# magnetorquer_board_CURRENT.net
KiCad netlist of a schematic drawn in EAGLE
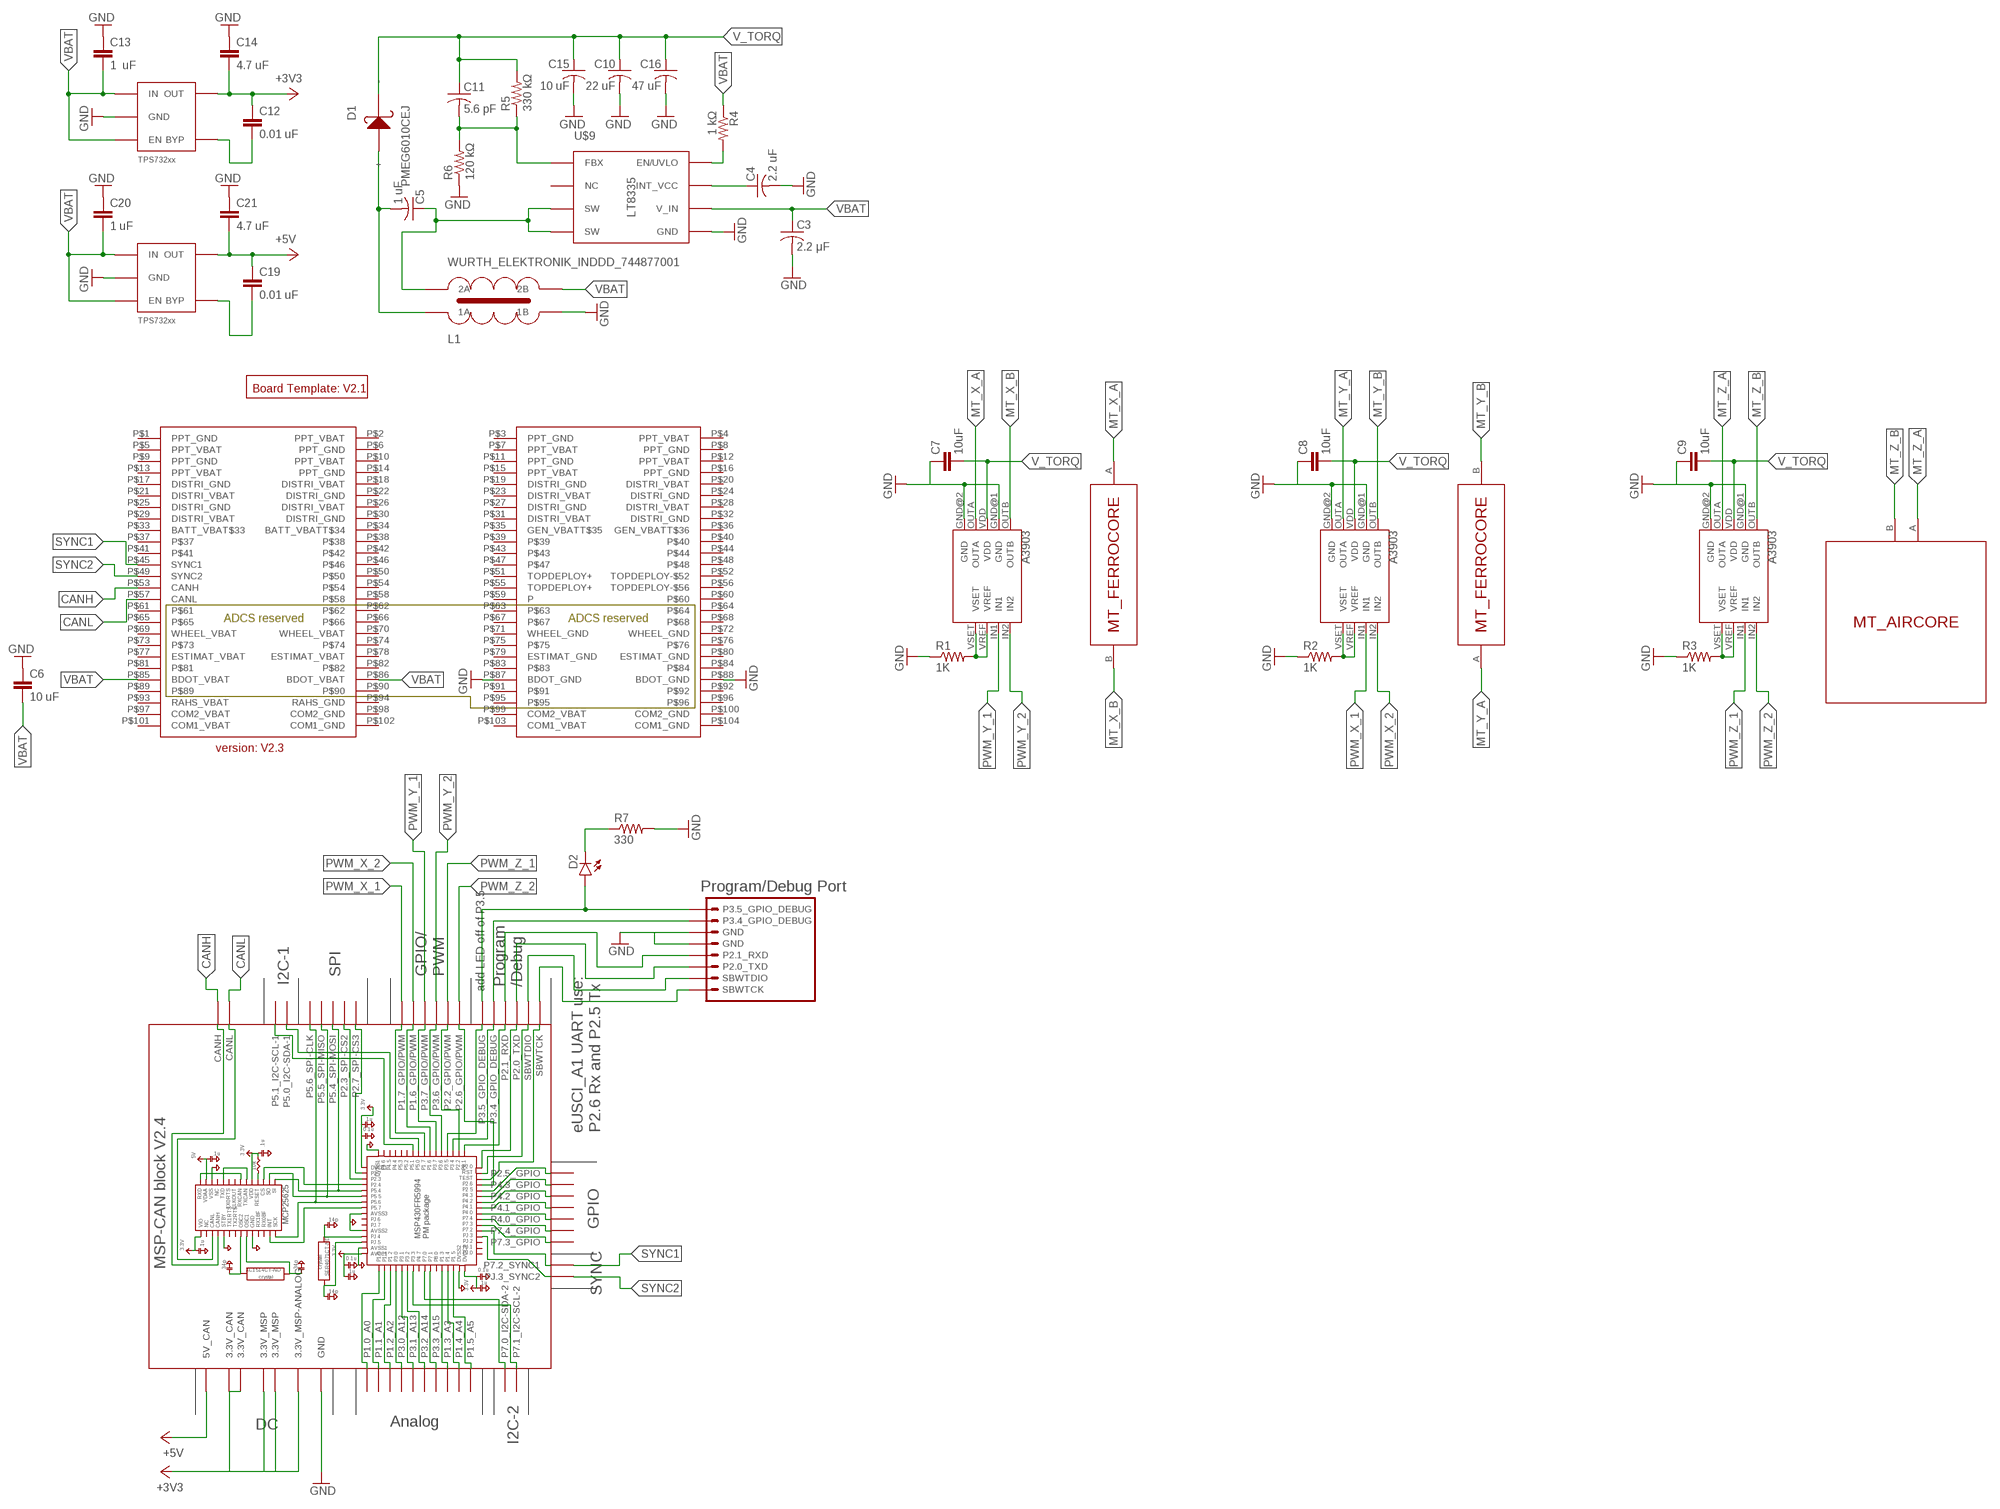
[diagram p0: schematic, sheet 1]

(export (version "E")
  (design (tool "Eeschema 10.0.6"))
  (components
    (comp (ref "C3")
      (value "2.2 μF")
      (footprint "eagle-import:C0805")
      (libsource (lib "eagle-import") (part "C-USC0805"))
    )
    (comp (ref "C4")
      (value "2.2 uF")
      (footprint "eagle-import:C0805")
      (libsource (lib "eagle-import") (part "C-USC0805"))
    )
    (comp (ref "C5")
      (value "1 uF")
      (footprint "eagle-import:C0805")
      (libsource (lib "eagle-import") (part "C-USC0805"))
    )
    (comp (ref "C6")
      (value "10 uF")
      (footprint "eagle-import:0805")
      (libsource (lib "eagle-import") (part "CAPACITOR0805"))
    )
    (comp (ref "C7")
      (value "10uF")
      (footprint "eagle-import:0805")
      (libsource (lib "eagle-import") (part "CAPACITOR0805"))
    )
    (comp (ref "C8")
      (value "10uF")
      (footprint "eagle-import:0805")
      (libsource (lib "eagle-import") (part "CAPACITOR0805"))
    )
    (comp (ref "C9")
      (value "10uF")
      (footprint "eagle-import:0805")
      (libsource (lib "eagle-import") (part "CAPACITOR0805"))
    )
    (comp (ref "C10")
      (value "22 uF")
      (footprint "eagle-import:C1206")
      (libsource (lib "eagle-import") (part "C-USC1206"))
    )
    (comp (ref "C11")
      (value "5.6 pF")
      (footprint "eagle-import:C0805")
      (libsource (lib "eagle-import") (part "C-USC0805"))
    )
    (comp (ref "C12")
      (value "0.01 uF")
      (footprint "eagle-import:0805")
      (libsource (lib "eagle-import") (part "CAPACITOR0805"))
    )
    (comp (ref "C13")
      (value "1 uF")
      (footprint "eagle-import:0805")
      (libsource (lib "eagle-import") (part "CAPACITOR0805"))
    )
    (comp (ref "C14")
      (value "4.7 uF")
      (footprint "eagle-import:0805")
      (libsource (lib "eagle-import") (part "CAPACITOR0805"))
    )
    (comp (ref "C15")
      (value "10 uF")
      (footprint "eagle-import:C0805")
      (libsource (lib "eagle-import") (part "C-USC0805"))
    )
    (comp (ref "C16")
      (value "47 uF")
      (footprint "eagle-import:C1206")
      (libsource (lib "eagle-import") (part "C-USC1206"))
    )
    (comp (ref "C19")
      (value "0.01 uF")
      (footprint "eagle-import:0805")
      (libsource (lib "eagle-import") (part "CAPACITOR0805"))
    )
    (comp (ref "C20")
      (value "1 uF")
      (footprint "eagle-import:0805")
      (libsource (lib "eagle-import") (part "CAPACITOR0805"))
    )
    (comp (ref "C21")
      (value "4.7 uF")
      (footprint "eagle-import:0805")
      (libsource (lib "eagle-import") (part "CAPACITOR0805"))
    )
    (comp (ref "D1")
      (value "PMEG6010CEJ")
      (footprint "eagle-import:SC-90")
      (libsource (lib "eagle-import") (part "PMEG6010CEJ"))
    )
    (comp (ref "D2")
      (value "LED")
      (footprint "eagle-import:LED-1206")
      (libsource (lib "eagle-import") (part "LED"))
    )
    (comp (ref "L1")
      (value "WURTH_ELEKTRONIK_INDDD_744877001")
      (footprint "eagle-import:WURTH_ELEKTRONIK_INDDD_744877001")
      (libsource (lib "eagle-import") (part "WURTH_ELEKTRONIK_INDDD_744877001"))
    )
    (comp (ref "LDO_3V1")
      (value "TPS732XX")
      (footprint "eagle-import:SOT-23-5")
      (libsource (lib "eagle-import") (part "TPS732XX"))
    )
    (comp (ref "LDO_5V1")
      (value "TPS732XX")
      (footprint "eagle-import:SOT-23-5")
      (libsource (lib "eagle-import") (part "TPS732XX"))
    )
    (comp (ref "R1")
      (value "1K")
      (footprint "eagle-import:R0603")
      (libsource (lib "eagle-import") (part "R-US_R0603"))
    )
    (comp (ref "R2")
      (value "1K")
      (footprint "eagle-import:R0603")
      (libsource (lib "eagle-import") (part "R-US_R0603"))
    )
    (comp (ref "R3")
      (value "1K")
      (footprint "eagle-import:R0603")
      (libsource (lib "eagle-import") (part "R-US_R0603"))
    )
    (comp (ref "R4")
      (value "1 kΩ")
      (footprint "eagle-import:0805")
      (libsource (lib "eagle-import") (part "RESISTOR0805"))
    )
    (comp (ref "R5")
      (value "330 kΩ")
      (footprint "eagle-import:0805")
      (libsource (lib "eagle-import") (part "RESISTOR0805"))
    )
    (comp (ref "R6")
      (value "120 kΩ")
      (footprint "eagle-import:0805")
      (libsource (lib "eagle-import") (part "RESISTOR0805"))
    )
    (comp (ref "R7")
      (value "330")
      (footprint "eagle-import:0805")
      (libsource (lib "eagle-import") (part "RESISTOR0805"))
    )
    (comp (ref "U$1")
      (value "PC104_CONNECTOR")
      (footprint "eagle-import:PC104_CONNECTOR")
      (libsource (lib "eagle-import") (part "PC104_CONNECTOR"))
    )
    (comp (ref "U$2")
      (value "BOARD_TEMPLATE1")
      (footprint "eagle-import:BOARD_TEMPLATE")
      (libsource (lib "eagle-import") (part "BOARD_TEMPLATE1"))
    )
    (comp (ref "U$3")
      (value "MT_AIRCORE")
      (footprint "eagle-import:MT_AIRCORE")
      (libsource (lib "eagle-import") (part "MT_AIRCORE"))
    )
    (comp (ref "U$4")
      (value "MT_FERROCORE")
      (footprint "eagle-import:MT_FERROCORE")
      (libsource (lib "eagle-import") (part "MT_FERROCORE"))
    )
    (comp (ref "U$5")
      (value "MT_FERROCORE")
      (footprint "eagle-import:MT_FERROCORE")
      (libsource (lib "eagle-import") (part "MT_FERROCORE"))
    )
    (comp (ref "U$7")
      (value "MSP-CAN_BLOCK")
      (footprint "eagle-import:MSP-CAN_BLOCK")
      (libsource (lib "eagle-import") (part "MSP-CAN_BLOCK"))
    )
    (comp (ref "U$8")
      (value "PROGRAM/DEBUG_PORT")
      (footprint "eagle-import:1X08_CONNECTOR")
      (libsource (lib "eagle-import") (part "PROGRAM/DEBUG_PORT"))
    )
    (comp (ref "U$9")
      (value "LT8335")
      (footprint "eagle-import:DDB")
      (libsource (lib "eagle-import") (part "LT8335"))
    )
    (comp (ref "U1")
      (value "A3903")
      (footprint "eagle-import:DFN-8EE")
      (libsource (lib "eagle-import") (part "A3903"))
    )
    (comp (ref "U2")
      (value "A3903")
      (footprint "eagle-import:DFN-8EE")
      (libsource (lib "eagle-import") (part "A3903"))
    )
    (comp (ref "U3")
      (value "A3903")
      (footprint "eagle-import:DFN-8EE")
      (libsource (lib "eagle-import") (part "A3903"))
    )
  )
  (nets
    (net (code "1") (name "+3V3") (class "Default")
      (node (ref "C12") (pin "1") (pinfunction "1_1") (pintype "passive"))
      (node (ref "C14") (pin "2") (pinfunction "2_2") (pintype "passive"))
      (node (ref "LDO_3V1") (pin "P$5") (pinfunction "OUT_P$5") (pintype "bidirectional"))
      (node (ref "U$7") (pin "3.3V@CAN1") (pinfunction "3.3V_CAN_3.3V@CAN1") (pintype "bidirectional"))
      (node (ref "U$7") (pin "3.3V@CAN2") (pinfunction "3.3V_CAN_3.3V@CAN2") (pintype "bidirectional"))
      (node (ref "U$7") (pin "3.3V@MSP1") (pinfunction "3.3V_MSP_3.3V@MSP1") (pintype "bidirectional"))
      (node (ref "U$7") (pin "3.3V@MSP2") (pinfunction "3.3V_MSP_3.3V@MSP2") (pintype "bidirectional"))
      (node (ref "U$7") (pin "3.3V_ANALOG@MSP2") (pinfunction "3.3V_MSP-ANALOG_3.3V_ANALOG@MSP2") (pintype "bidirectional"))
    )
    (net (code "2") (name "+5V") (class "Default")
      (node (ref "C19") (pin "1") (pinfunction "1_1") (pintype "passive"))
      (node (ref "C21") (pin "2") (pinfunction "2_2") (pintype "passive"))
      (node (ref "LDO_5V1") (pin "P$5") (pinfunction "OUT_P$5") (pintype "bidirectional"))
      (node (ref "U$7") (pin "5V") (pinfunction "5V_CAN_5V") (pintype "bidirectional"))
    )
    (net (code "3") (name "CANH") (class "Default")
      (node (ref "U$1") (pin "P$53") (pinfunction "CANH_P$53") (pintype "bidirectional"))
      (node (ref "U$7") (pin "CANH") (pinfunction "CANH_CANH") (pintype "bidirectional"))
    )
    (net (code "4") (name "CANL") (class "Default")
      (node (ref "U$1") (pin "P$57") (pinfunction "CANL_P$57") (pintype "bidirectional"))
      (node (ref "U$7") (pin "CANL") (pinfunction "CANL_CANL") (pintype "bidirectional"))
    )
    (net (code "5") (name "GND") (class "Default")
      (node (ref "C10") (pin "2") (pinfunction "2_2") (pintype "passive"))
      (node (ref "C13") (pin "1") (pinfunction "1_1") (pintype "passive"))
      (node (ref "C14") (pin "1") (pinfunction "1_1") (pintype "passive"))
      (node (ref "C15") (pin "2") (pinfunction "2_2") (pintype "passive"))
      (node (ref "C16") (pin "2") (pinfunction "2_2") (pintype "passive"))
      (node (ref "C20") (pin "1") (pinfunction "1_1") (pintype "passive"))
      (node (ref "C21") (pin "1") (pinfunction "1_1") (pintype "passive"))
      (node (ref "C3") (pin "2") (pinfunction "2_2") (pintype "passive"))
      (node (ref "C4") (pin "2") (pinfunction "2_2") (pintype "passive"))
      (node (ref "C6") (pin "1") (pinfunction "1_1") (pintype "passive"))
      (node (ref "C7") (pin "1") (pinfunction "1_1") (pintype "passive"))
      (node (ref "C8") (pin "1") (pinfunction "1_1") (pintype "passive"))
      (node (ref "C9") (pin "1") (pinfunction "1_1") (pintype "passive"))
      (node (ref "L1") (pin "P$2") (pinfunction "1B_P$2") (pintype "bidirectional"))
      (node (ref "LDO_3V1") (pin "P$2") (pinfunction "GND_P$2") (pintype "bidirectional"))
      (node (ref "LDO_5V1") (pin "P$2") (pinfunction "GND_P$2") (pintype "bidirectional"))
      (node (ref "R1") (pin "1") (pinfunction "1_1") (pintype "passive"))
      (node (ref "R2") (pin "1") (pinfunction "1_1") (pintype "passive"))
      (node (ref "R3") (pin "1") (pinfunction "1_1") (pintype "passive"))
      (node (ref "R6") (pin "1") (pinfunction "1_1") (pintype "passive"))
      (node (ref "R7") (pin "2") (pinfunction "2_2") (pintype "passive"))
      (node (ref "U$1") (pin "P$87") (pinfunction "BDOT_GND_P$87") (pintype "bidirectional"))
      (node (ref "U$1") (pin "P$88") (pinfunction "BDOT_GND_P$88") (pintype "bidirectional"))
      (node (ref "U$7") (pin "GND@1") (pinfunction "GND_GND@1") (pintype "bidirectional"))
      (node (ref "U$7") (pin "GND@10") (pinfunction "GND_GND@10") (pintype "bidirectional"))
      (node (ref "U$7") (pin "GND@11") (pinfunction "GND_GND@11") (pintype "bidirectional"))
      (node (ref "U$7") (pin "GND@12") (pinfunction "GND_GND@12") (pintype "bidirectional"))
      (node (ref "U$7") (pin "GND@13") (pinfunction "GND_GND@13") (pintype "bidirectional"))
      (node (ref "U$7") (pin "GND@14") (pinfunction "GND_GND@14") (pintype "bidirectional"))
      (node (ref "U$7") (pin "GND@15") (pinfunction "GND_GND@15") (pintype "bidirectional"))
      (node (ref "U$7") (pin "GND@16") (pinfunction "GND_GND@16") (pintype "bidirectional"))
      (node (ref "U$7") (pin "GND@17") (pinfunction "GND_GND@17") (pintype "bidirectional"))
      (node (ref "U$7") (pin "GND@2") (pinfunction "GND_GND@2") (pintype "bidirectional"))
      (node (ref "U$7") (pin "GND@26") (pinfunction "GND_GND@26") (pintype "bidirectional"))
      (node (ref "U$7") (pin "GND@3") (pinfunction "GND_GND@3") (pintype "bidirectional"))
      (node (ref "U$7") (pin "GND@4") (pinfunction "GND_GND@4") (pintype "bidirectional"))
      (node (ref "U$7") (pin "GND@5") (pinfunction "GND_GND@5") (pintype "bidirectional"))
      (node (ref "U$7") (pin "GND@7") (pinfunction "GND_GND@7") (pintype "bidirectional"))
      (node (ref "U$7") (pin "GND@8") (pinfunction "GND_GND@8") (pintype "bidirectional"))
      (node (ref "U$7") (pin "GND@9") (pinfunction "GND_GND@9") (pintype "bidirectional"))
      (node (ref "U$8") (pin "5") (pinfunction "GND_5") (pintype "bidirectional"))
      (node (ref "U$8") (pin "6") (pinfunction "GND_6") (pintype "bidirectional"))
      (node (ref "U$9") (pin "GND") (pinfunction "GND_GND") (pintype "bidirectional"))
      (node (ref "U$9") (pin "P$5") (pinfunction "GND_P$5") (pintype "bidirectional"))
      (node (ref "U1") (pin "GND@1") (pinfunction "GND_GND@1") (pintype "power_in"))
      (node (ref "U1") (pin "GND@2") (pinfunction "GND_GND@2") (pintype "power_in"))
      (node (ref "U2") (pin "GND@1") (pinfunction "GND_GND@1") (pintype "power_in"))
      (node (ref "U2") (pin "GND@2") (pinfunction "GND_GND@2") (pintype "power_in"))
      (node (ref "U3") (pin "GND@1") (pinfunction "GND_GND@1") (pintype "power_in"))
      (node (ref "U3") (pin "GND@2") (pinfunction "GND_GND@2") (pintype "power_in"))
    )
    (net (code "6") (name "MT_X_A") (class "Default")
      (node (ref "U$4") (pin "A") (pinfunction "A_A") (pintype "bidirectional"))
      (node (ref "U1") (pin "OUTA") (pinfunction "OUTA_OUTA") (pintype "output"))
    )
    (net (code "7") (name "MT_X_B") (class "Default")
      (node (ref "U$4") (pin "B") (pinfunction "B_B") (pintype "bidirectional"))
      (node (ref "U1") (pin "OUTB") (pinfunction "OUTB_OUTB") (pintype "output"))
    )
    (net (code "8") (name "MT_Y_A") (class "Default")
      (node (ref "U$5") (pin "A") (pinfunction "A_A") (pintype "bidirectional"))
      (node (ref "U2") (pin "OUTA") (pinfunction "OUTA_OUTA") (pintype "output"))
    )
    (net (code "9") (name "MT_Y_B") (class "Default")
      (node (ref "U$5") (pin "B") (pinfunction "B_B") (pintype "bidirectional"))
      (node (ref "U2") (pin "OUTB") (pinfunction "OUTB_OUTB") (pintype "output"))
    )
    (net (code "10") (name "MT_Z_A") (class "Default")
      (node (ref "U$3") (pin "A") (pinfunction "A_A") (pintype "bidirectional"))
      (node (ref "U3") (pin "OUTA") (pinfunction "OUTA_OUTA") (pintype "output"))
    )
    (net (code "11") (name "MT_Z_B") (class "Default")
      (node (ref "U$3") (pin "B") (pinfunction "B_B") (pintype "bidirectional"))
      (node (ref "U3") (pin "OUTB") (pinfunction "OUTB_OUTB") (pintype "output"))
    )
    (net (code "12") (name "Net-(D1-+)") (class "Default")
      (node (ref "C5") (pin "2") (pinfunction "2_2") (pintype "passive"))
      (node (ref "D1") (pin "P$1") (pinfunction "+_P$1") (pintype "bidirectional"))
      (node (ref "L1") (pin "P$1") (pinfunction "1A_P$1") (pintype "bidirectional"))
    )
    (net (code "13") (name "Net-(D2-PadC)") (class "Default")
      (node (ref "D2") (pin "C") (pinfunction "C_C") (pintype "passive"))
      (node (ref "R7") (pin "1") (pinfunction "1_1") (pintype "passive"))
    )
    (net (code "14") (name "Net-(L1-2A)") (class "Default")
      (node (ref "C5") (pin "1") (pinfunction "1_1") (pintype "passive"))
      (node (ref "L1") (pin "P$3") (pinfunction "2A_P$3") (pintype "bidirectional"))
      (node (ref "U$9") (pin "P$3") (pinfunction "SW_P$3") (pintype "bidirectional"))
      (node (ref "U$9") (pin "P$4") (pinfunction "SW_P$4") (pintype "bidirectional"))
    )
    (net (code "15") (name "Net-(LDO_3V1-BYP)") (class "Default")
      (node (ref "C12") (pin "2") (pinfunction "2_2") (pintype "passive"))
      (node (ref "LDO_3V1") (pin "P$4") (pinfunction "BYP_P$4") (pintype "bidirectional"))
    )
    (net (code "16") (name "Net-(LDO_5V1-BYP)") (class "Default")
      (node (ref "C19") (pin "2") (pinfunction "2_2") (pintype "passive"))
      (node (ref "LDO_5V1") (pin "P$4") (pinfunction "BYP_P$4") (pintype "bidirectional"))
    )
    (net (code "17") (name "Net-(R1-Pad2)") (class "Default")
      (node (ref "R1") (pin "2") (pinfunction "2_2") (pintype "passive"))
      (node (ref "U1") (pin "VREF") (pinfunction "VREF_VREF") (pintype "power_in"))
      (node (ref "U1") (pin "VSET") (pinfunction "VSET_VSET") (pintype "bidirectional"))
    )
    (net (code "18") (name "Net-(R2-Pad2)") (class "Default")
      (node (ref "R2") (pin "2") (pinfunction "2_2") (pintype "passive"))
      (node (ref "U2") (pin "VREF") (pinfunction "VREF_VREF") (pintype "power_in"))
      (node (ref "U2") (pin "VSET") (pinfunction "VSET_VSET") (pintype "bidirectional"))
    )
    (net (code "19") (name "Net-(R3-Pad2)") (class "Default")
      (node (ref "R3") (pin "2") (pinfunction "2_2") (pintype "passive"))
      (node (ref "U3") (pin "VREF") (pinfunction "VREF_VREF") (pintype "power_in"))
      (node (ref "U3") (pin "VSET") (pinfunction "VSET_VSET") (pintype "bidirectional"))
    )
    (net (code "20") (name "Net-(U$7-PadSBWTCK)") (class "Default")
      (node (ref "U$7") (pin "SBWTCK") (pinfunction "SBWTCK_SBWTCK") (pintype "bidirectional"))
      (node (ref "U$8") (pin "SBWTCK") (pinfunction "SBWTCK_SBWTCK") (pintype "bidirectional"))
    )
    (net (code "21") (name "Net-(U$8-P2.0_TXD)") (class "Default")
      (node (ref "U$7") (pin "P2.0_TXD") (pinfunction "P2.0_TXD_P2.0_TXD") (pintype "bidirectional"))
      (node (ref "U$8") (pin "3") (pinfunction "P2.0_TXD_3") (pintype "bidirectional"))
    )
    (net (code "22") (name "Net-(U$8-P2.1_RXD)") (class "Default")
      (node (ref "U$7") (pin "P2.1_RXD") (pinfunction "P2.1_RXD_P2.1_RXD") (pintype "bidirectional"))
      (node (ref "U$8") (pin "4") (pinfunction "P2.1_RXD_4") (pintype "bidirectional"))
    )
    (net (code "23") (name "Net-(U$8-P3.4_GPIO_DEBUG)") (class "Default")
      (node (ref "U$7") (pin "P3.4_GPIO_DEBUG") (pinfunction "P3.4_GPIO_DEBUG_P3.4_GPIO_DEBUG") (pintype "bidirectional"))
      (node (ref "U$8") (pin "7") (pinfunction "P3.4_GPIO_DEBUG_7") (pintype "bidirectional"))
    )
    (net (code "24") (name "Net-(U$8-P3.5_GPIO_DEBUG)") (class "Default")
      (node (ref "D2") (pin "A") (pinfunction "A_A") (pintype "passive"))
      (node (ref "U$7") (pin "P3.5_GPIO_DEBUG") (pinfunction "P3.5_GPIO_DEBUG_P3.5_GPIO_DEBUG") (pintype "bidirectional"))
      (node (ref "U$8") (pin "8") (pinfunction "P3.5_GPIO_DEBUG_8") (pintype "bidirectional"))
    )
    (net (code "25") (name "Net-(U$8-SBWTDIO)") (class "Default")
      (node (ref "U$7") (pin "SBWTDIO") (pinfunction "SBWTDIO_SBWTDIO") (pintype "bidirectional"))
      (node (ref "U$8") (pin "2") (pinfunction "SBWTDIO_2") (pintype "bidirectional"))
    )
    (net (code "26") (name "Net-(U$9-EN{slash}UVLO)") (class "Default")
      (node (ref "R4") (pin "2") (pinfunction "2_2") (pintype "passive"))
      (node (ref "U$9") (pin "P$8") (pinfunction "EN/UVLO_P$8") (pintype "bidirectional"))
    )
    (net (code "27") (name "Net-(U$9-FBX)") (class "Default")
      (node (ref "C11") (pin "2") (pinfunction "2_2") (pintype "passive"))
      (node (ref "R5") (pin "1") (pinfunction "1_1") (pintype "passive"))
      (node (ref "R6") (pin "2") (pinfunction "2_2") (pintype "passive"))
      (node (ref "U$9") (pin "P$1") (pinfunction "FBX_P$1") (pintype "bidirectional"))
    )
    (net (code "28") (name "Net-(U$9-INT_VCC)") (class "Default")
      (node (ref "C4") (pin "1") (pinfunction "1_1") (pintype "passive"))
      (node (ref "U$9") (pin "P$7") (pinfunction "INT_VCC_P$7") (pintype "bidirectional"))
    )
    (net (code "29") (name "PWM_X_1") (class "Default")
      (node (ref "U$7") (pin "P1.7_GPIO/PWM") (pinfunction "P1.7_GPIO/PWM_P1.7_GPIO/PWM") (pintype "bidirectional"))
      (node (ref "U2") (pin "IN1") (pinfunction "IN1_IN1") (pintype "input"))
    )
    (net (code "30") (name "PWM_X_2") (class "Default")
      (node (ref "U$7") (pin "P1.6_GPIO/PWM") (pinfunction "P1.6_GPIO/PWM_P1.6_GPIO/PWM") (pintype "bidirectional"))
      (node (ref "U2") (pin "IN2") (pinfunction "IN2_IN2") (pintype "input"))
    )
    (net (code "31") (name "PWM_Y_1") (class "Default")
      (node (ref "U$7") (pin "P3.7_GPIO/PWM") (pinfunction "P3.7_GPIO/PWM_P3.7_GPIO/PWM") (pintype "bidirectional"))
      (node (ref "U1") (pin "IN1") (pinfunction "IN1_IN1") (pintype "input"))
    )
    (net (code "32") (name "PWM_Y_2") (class "Default")
      (node (ref "U$7") (pin "P3.6_GPIO/PWM") (pinfunction "P3.6_GPIO/PWM_P3.6_GPIO/PWM") (pintype "bidirectional"))
      (node (ref "U1") (pin "IN2") (pinfunction "IN2_IN2") (pintype "input"))
    )
    (net (code "33") (name "PWM_Z_1") (class "Default")
      (node (ref "U$7") (pin "P2.2_GPIO/PWM") (pinfunction "P2.2_GPIO/PWM_P2.2_GPIO/PWM") (pintype "bidirectional"))
      (node (ref "U3") (pin "IN1") (pinfunction "IN1_IN1") (pintype "input"))
    )
    (net (code "34") (name "PWM_Z_2") (class "Default")
      (node (ref "U$7") (pin "P2.6_GPIO/PWM") (pinfunction "P2.6_GPIO/PWM_P2.6_GPIO/PWM") (pintype "bidirectional"))
      (node (ref "U3") (pin "IN2") (pinfunction "IN2_IN2") (pintype "input"))
    )
    (net (code "35") (name "SYNC1") (class "Default")
      (node (ref "U$1") (pin "P$45") (pinfunction "SYNC1_P$45") (pintype "bidirectional"))
      (node (ref "U$7") (pin "P7.2_SYNC1") (pinfunction "P7.2_SYNC1_P7.2_SYNC1") (pintype "bidirectional"))
    )
    (net (code "36") (name "SYNC2") (class "Default")
      (node (ref "U$1") (pin "P$49") (pinfunction "SYNC2_P$49") (pintype "bidirectional"))
      (node (ref "U$7") (pin "PJ.3_SYNC2") (pinfunction "PJ.3_SYNC2_PJ.3_SYNC2") (pintype "bidirectional"))
    )
    (net (code "37") (name "VBAT") (class "Default")
      (node (ref "C13") (pin "2") (pinfunction "2_2") (pintype "passive"))
      (node (ref "C20") (pin "2") (pinfunction "2_2") (pintype "passive"))
      (node (ref "C3") (pin "1") (pinfunction "1_1") (pintype "passive"))
      (node (ref "C6") (pin "2") (pinfunction "2_2") (pintype "passive"))
      (node (ref "L1") (pin "P$4") (pinfunction "2B_P$4") (pintype "bidirectional"))
      (node (ref "LDO_3V1") (pin "P$1") (pinfunction "IN_P$1") (pintype "bidirectional"))
      (node (ref "LDO_3V1") (pin "P$3") (pinfunction "EN_P$3") (pintype "bidirectional"))
      (node (ref "LDO_5V1") (pin "P$1") (pinfunction "IN_P$1") (pintype "bidirectional"))
      (node (ref "LDO_5V1") (pin "P$3") (pinfunction "EN_P$3") (pintype "bidirectional"))
      (node (ref "R4") (pin "1") (pinfunction "1_1") (pintype "passive"))
      (node (ref "U$1") (pin "P$85") (pinfunction "BDOT_VBAT_P$85") (pintype "bidirectional"))
      (node (ref "U$1") (pin "P$86") (pinfunction "BDOT_VBAT_P$86") (pintype "bidirectional"))
      (node (ref "U$9") (pin "P$6") (pinfunction "V_IN_P$6") (pintype "bidirectional"))
    )
    (net (code "38") (name "V_TORQ") (class "Default")
      (node (ref "C10") (pin "1") (pinfunction "1_1") (pintype "passive"))
      (node (ref "C11") (pin "1") (pinfunction "1_1") (pintype "passive"))
      (node (ref "C15") (pin "1") (pinfunction "1_1") (pintype "passive"))
      (node (ref "C16") (pin "1") (pinfunction "1_1") (pintype "passive"))
      (node (ref "C7") (pin "2") (pinfunction "2_2") (pintype "passive"))
      (node (ref "C8") (pin "2") (pinfunction "2_2") (pintype "passive"))
      (node (ref "C9") (pin "2") (pinfunction "2_2") (pintype "passive"))
      (node (ref "D1") (pin "P$2") (pinfunction "-_P$2") (pintype "bidirectional"))
      (node (ref "R5") (pin "2") (pinfunction "2_2") (pintype "passive"))
      (node (ref "U1") (pin "VDD") (pinfunction "VDD_VDD") (pintype "power_in"))
      (node (ref "U2") (pin "VDD") (pinfunction "VDD_VDD") (pintype "power_in"))
      (node (ref "U3") (pin "VDD") (pinfunction "VDD_VDD") (pintype "power_in"))
    )
    (net (code "39") (name "unconnected-(U$1-BATT_VBAT$33-PadP$33)") (class "Default")
      (node (ref "U$1") (pin "P$33") (pinfunction "BATT_VBAT$33_P$33") (pintype "bidirectional"))
    )
    (net (code "40") (name "unconnected-(U$1-BATT_VBATT$34-PadP$34)") (class "Default")
      (node (ref "U$1") (pin "P$34") (pinfunction "BATT_VBATT$34_P$34") (pintype "bidirectional"))
    )
    (net (code "41") (name "unconnected-(U$1-COM1_GND-PadP$102)") (class "Default")
      (node (ref "U$1") (pin "P$102") (pinfunction "COM1_GND_P$102") (pintype "bidirectional"))
    )
    (net (code "42") (name "unconnected-(U$1-COM1_GND-PadP$104)") (class "Default")
      (node (ref "U$1") (pin "P$104") (pinfunction "COM1_GND_P$104") (pintype "bidirectional"))
    )
    (net (code "43") (name "unconnected-(U$1-COM1_VBAT-PadP$101)") (class "Default")
      (node (ref "U$1") (pin "P$101") (pinfunction "COM1_VBAT_P$101") (pintype "bidirectional"))
    )
    (net (code "44") (name "unconnected-(U$1-COM1_VBAT-PadP$103)") (class "Default")
      (node (ref "U$1") (pin "P$103") (pinfunction "COM1_VBAT_P$103") (pintype "bidirectional"))
    )
    (net (code "45") (name "unconnected-(U$1-COM2_GND-PadP$98)") (class "Default")
      (node (ref "U$1") (pin "P$98") (pinfunction "COM2_GND_P$98") (pintype "bidirectional"))
    )
    (net (code "46") (name "unconnected-(U$1-COM2_GND-PadP$100)") (class "Default")
      (node (ref "U$1") (pin "P$100") (pinfunction "COM2_GND_P$100") (pintype "bidirectional"))
    )
    (net (code "47") (name "unconnected-(U$1-COM2_VBAT-PadP$97)") (class "Default")
      (node (ref "U$1") (pin "P$97") (pinfunction "COM2_VBAT_P$97") (pintype "bidirectional"))
    )
    (net (code "48") (name "unconnected-(U$1-COM2_VBAT-PadP$99)") (class "Default")
      (node (ref "U$1") (pin "P$99") (pinfunction "COM2_VBAT_P$99") (pintype "bidirectional"))
    )
    (net (code "49") (name "unconnected-(U$1-DISTRI_GND-PadP$17)") (class "Default")
      (node (ref "U$1") (pin "P$17") (pinfunction "DISTRI_GND_P$17") (pintype "bidirectional"))
    )
    (net (code "50") (name "unconnected-(U$1-DISTRI_GND-PadP$19)") (class "Default")
      (node (ref "U$1") (pin "P$19") (pinfunction "DISTRI_GND_P$19") (pintype "bidirectional"))
    )
    (net (code "51") (name "unconnected-(U$1-DISTRI_GND-PadP$22)") (class "Default")
      (node (ref "U$1") (pin "P$22") (pinfunction "DISTRI_GND_P$22") (pintype "bidirectional"))
    )
    (net (code "52") (name "unconnected-(U$1-DISTRI_GND-PadP$24)") (class "Default")
      (node (ref "U$1") (pin "P$24") (pinfunction "DISTRI_GND_P$24") (pintype "bidirectional"))
    )
    (net (code "53") (name "unconnected-(U$1-DISTRI_GND-PadP$25)") (class "Default")
      (node (ref "U$1") (pin "P$25") (pinfunction "DISTRI_GND_P$25") (pintype "bidirectional"))
    )
    (net (code "54") (name "unconnected-(U$1-DISTRI_GND-PadP$27)") (class "Default")
      (node (ref "U$1") (pin "P$27") (pinfunction "DISTRI_GND_P$27") (pintype "bidirectional"))
    )
    (net (code "55") (name "unconnected-(U$1-DISTRI_GND-PadP$30)") (class "Default")
      (node (ref "U$1") (pin "P$30") (pinfunction "DISTRI_GND_P$30") (pintype "bidirectional"))
    )
    (net (code "56") (name "unconnected-(U$1-DISTRI_GND-PadP$32)") (class "Default")
      (node (ref "U$1") (pin "P$32") (pinfunction "DISTRI_GND_P$32") (pintype "bidirectional"))
    )
    (net (code "57") (name "unconnected-(U$1-DISTRI_VBAT-PadP$18)") (class "Default")
      (node (ref "U$1") (pin "P$18") (pinfunction "DISTRI_VBAT_P$18") (pintype "bidirectional"))
    )
    (net (code "58") (name "unconnected-(U$1-DISTRI_VBAT-PadP$20)") (class "Default")
      (node (ref "U$1") (pin "P$20") (pinfunction "DISTRI_VBAT_P$20") (pintype "bidirectional"))
    )
    (net (code "59") (name "unconnected-(U$1-DISTRI_VBAT-PadP$21)") (class "Default")
      (node (ref "U$1") (pin "P$21") (pinfunction "DISTRI_VBAT_P$21") (pintype "bidirectional"))
    )
    (net (code "60") (name "unconnected-(U$1-DISTRI_VBAT-PadP$23)") (class "Default")
      (node (ref "U$1") (pin "P$23") (pinfunction "DISTRI_VBAT_P$23") (pintype "bidirectional"))
    )
    (net (code "61") (name "unconnected-(U$1-DISTRI_VBAT-PadP$26)") (class "Default")
      (node (ref "U$1") (pin "P$26") (pinfunction "DISTRI_VBAT_P$26") (pintype "bidirectional"))
    )
    (net (code "62") (name "unconnected-(U$1-DISTRI_VBAT-PadP$28)") (class "Default")
      (node (ref "U$1") (pin "P$28") (pinfunction "DISTRI_VBAT_P$28") (pintype "bidirectional"))
    )
    (net (code "63") (name "unconnected-(U$1-DISTRI_VBAT-PadP$29)") (class "Default")
      (node (ref "U$1") (pin "P$29") (pinfunction "DISTRI_VBAT_P$29") (pintype "bidirectional"))
    )
    (net (code "64") (name "unconnected-(U$1-DISTRI_VBAT-PadP$31)") (class "Default")
      (node (ref "U$1") (pin "P$31") (pinfunction "DISTRI_VBAT_P$31") (pintype "bidirectional"))
    )
    (net (code "65") (name "unconnected-(U$1-ESTIMAT_GND-PadP$79)") (class "Default")
      (node (ref "U$1") (pin "P$79") (pinfunction "ESTIMAT_GND_P$79") (pintype "bidirectional"))
    )
    (net (code "66") (name "unconnected-(U$1-ESTIMAT_GND-PadP$80)") (class "Default")
      (node (ref "U$1") (pin "P$80") (pinfunction "ESTIMAT_GND_P$80") (pintype "bidirectional"))
    )
    (net (code "67") (name "unconnected-(U$1-ESTIMAT_VBAT-PadP$77)") (class "Default")
      (node (ref "U$1") (pin "P$77") (pinfunction "ESTIMAT_VBAT_P$77") (pintype "bidirectional"))
    )
    (net (code "68") (name "unconnected-(U$1-ESTIMAT_VBAT-PadP$78)") (class "Default")
      (node (ref "U$1") (pin "P$78") (pinfunction "ESTIMAT_VBAT_P$78") (pintype "bidirectional"))
    )
    (net (code "69") (name "unconnected-(U$1-GEN_VBATT$35-PadP$35)") (class "Default")
      (node (ref "U$1") (pin "P$35") (pinfunction "GEN_VBATT$35_P$35") (pintype "bidirectional"))
    )
    (net (code "70") (name "unconnected-(U$1-GEN_VBATT$36-PadP$36)") (class "Default")
      (node (ref "U$1") (pin "P$36") (pinfunction "GEN_VBATT$36_P$36") (pintype "bidirectional"))
    )
    (net (code "71") (name "unconnected-(U$1-P-PadP$59)") (class "Default")
      (node (ref "U$1") (pin "P$59") (pinfunction "P_P$59") (pintype "bidirectional"))
    )
    (net (code "72") (name "unconnected-(U$1-PPT_GND-PadP$1)") (class "Default")
      (node (ref "U$1") (pin "P$1") (pinfunction "PPT_GND_P$1") (pintype "bidirectional"))
    )
    (net (code "73") (name "unconnected-(U$1-PPT_GND-PadP$3)") (class "Default")
      (node (ref "U$1") (pin "P$3") (pinfunction "PPT_GND_P$3") (pintype "bidirectional"))
    )
    (net (code "74") (name "unconnected-(U$1-PPT_GND-PadP$6)") (class "Default")
      (node (ref "U$1") (pin "P$6") (pinfunction "PPT_GND_P$6") (pintype "bidirectional"))
    )
    (net (code "75") (name "unconnected-(U$1-PPT_GND-PadP$8)") (class "Default")
      (node (ref "U$1") (pin "P$8") (pinfunction "PPT_GND_P$8") (pintype "bidirectional"))
    )
    (net (code "76") (name "unconnected-(U$1-PPT_GND-PadP$9)") (class "Default")
      (node (ref "U$1") (pin "P$9") (pinfunction "PPT_GND_P$9") (pintype "bidirectional"))
    )
    (net (code "77") (name "unconnected-(U$1-PPT_GND-PadP$11)") (class "Default")
      (node (ref "U$1") (pin "P$11") (pinfunction "PPT_GND_P$11") (pintype "bidirectional"))
    )
    (net (code "78") (name "unconnected-(U$1-PPT_GND-PadP$14)") (class "Default")
      (node (ref "U$1") (pin "P$14") (pinfunction "PPT_GND_P$14") (pintype "bidirectional"))
    )
    (net (code "79") (name "unconnected-(U$1-PPT_GND-PadP$16)") (class "Default")
      (node (ref "U$1") (pin "P$16") (pinfunction "PPT_GND_P$16") (pintype "bidirectional"))
    )
    (net (code "80") (name "unconnected-(U$1-PPT_VBAT-PadP$2)") (class "Default")
      (node (ref "U$1") (pin "P$2") (pinfunction "PPT_VBAT_P$2") (pintype "bidirectional"))
    )
    (net (code "81") (name "unconnected-(U$1-PPT_VBAT-PadP$4)") (class "Default")
      (node (ref "U$1") (pin "P$4") (pinfunction "PPT_VBAT_P$4") (pintype "bidirectional"))
    )
    (net (code "82") (name "unconnected-(U$1-PPT_VBAT-PadP$5)") (class "Default")
      (node (ref "U$1") (pin "P$5") (pinfunction "PPT_VBAT_P$5") (pintype "bidirectional"))
    )
    (net (code "83") (name "unconnected-(U$1-PPT_VBAT-PadP$7)") (class "Default")
      (node (ref "U$1") (pin "P$7") (pinfunction "PPT_VBAT_P$7") (pintype "bidirectional"))
    )
    (net (code "84") (name "unconnected-(U$1-PPT_VBAT-PadP$10)") (class "Default")
      (node (ref "U$1") (pin "P$10") (pinfunction "PPT_VBAT_P$10") (pintype "bidirectional"))
    )
    (net (code "85") (name "unconnected-(U$1-PPT_VBAT-PadP$12)") (class "Default")
      (node (ref "U$1") (pin "P$12") (pinfunction "PPT_VBAT_P$12") (pintype "bidirectional"))
    )
    (net (code "86") (name "unconnected-(U$1-PPT_VBAT-PadP$13)") (class "Default")
      (node (ref "U$1") (pin "P$13") (pinfunction "PPT_VBAT_P$13") (pintype "bidirectional"))
    )
    (net (code "87") (name "unconnected-(U$1-PPT_VBAT-PadP$15)") (class "Default")
      (node (ref "U$1") (pin "P$15") (pinfunction "PPT_VBAT_P$15") (pintype "bidirectional"))
    )
    (net (code "88") (name "unconnected-(U$1-PadP$37)") (class "Default")
      (node (ref "U$1") (pin "P$37") (pinfunction "P$37_P$37") (pintype "bidirectional"))
    )
    (net (code "89") (name "unconnected-(U$1-PadP$38)") (class "Default")
      (node (ref "U$1") (pin "P$38") (pinfunction "P$38_P$38") (pintype "bidirectional"))
    )
    (net (code "90") (name "unconnected-(U$1-PadP$39)") (class "Default")
      (node (ref "U$1") (pin "P$39") (pinfunction "P$39_P$39") (pintype "bidirectional"))
    )
    (net (code "91") (name "unconnected-(U$1-PadP$40)") (class "Default")
      (node (ref "U$1") (pin "P$40") (pinfunction "P$40_P$40") (pintype "bidirectional"))
    )
    (net (code "92") (name "unconnected-(U$1-PadP$41)") (class "Default")
      (node (ref "U$1") (pin "P$41") (pinfunction "P$41_P$41") (pintype "bidirectional"))
    )
    (net (code "93") (name "unconnected-(U$1-PadP$42)") (class "Default")
      (node (ref "U$1") (pin "P$42") (pinfunction "P$42_P$42") (pintype "bidirectional"))
    )
    (net (code "94") (name "unconnected-(U$1-PadP$43)") (class "Default")
      (node (ref "U$1") (pin "P$43") (pinfunction "P$43_P$43") (pintype "bidirectional"))
    )
    (net (code "95") (name "unconnected-(U$1-PadP$44)") (class "Default")
      (node (ref "U$1") (pin "P$44") (pinfunction "P$44_P$44") (pintype "bidirectional"))
    )
    (net (code "96") (name "unconnected-(U$1-PadP$46)") (class "Default")
      (node (ref "U$1") (pin "P$46") (pinfunction "P$46_P$46") (pintype "bidirectional"))
    )
    (net (code "97") (name "unconnected-(U$1-PadP$47)") (class "Default")
      (node (ref "U$1") (pin "P$47") (pinfunction "P$47_P$47") (pintype "bidirectional"))
    )
    (net (code "98") (name "unconnected-(U$1-PadP$48)") (class "Default")
      (node (ref "U$1") (pin "P$48") (pinfunction "P$48_P$48") (pintype "bidirectional"))
    )
    (net (code "99") (name "unconnected-(U$1-PadP$50)") (class "Default")
      (node (ref "U$1") (pin "P$50") (pinfunction "P$50_P$50") (pintype "bidirectional"))
    )
    (net (code "100") (name "unconnected-(U$1-PadP$54)") (class "Default")
      (node (ref "U$1") (pin "P$54") (pinfunction "P$54_P$54") (pintype "bidirectional"))
    )
    (net (code "101") (name "unconnected-(U$1-PadP$58)") (class "Default")
      (node (ref "U$1") (pin "P$58") (pinfunction "P$58_P$58") (pintype "bidirectional"))
    )
    (net (code "102") (name "unconnected-(U$1-PadP$60)") (class "Default")
      (node (ref "U$1") (pin "P$60") (pinfunction "P$60_P$60") (pintype "bidirectional"))
    )
    (net (code "103") (name "unconnected-(U$1-PadP$61)") (class "Default")
      (node (ref "U$1") (pin "P$61") (pinfunction "P$61_P$61") (pintype "bidirectional"))
    )
    (net (code "104") (name "unconnected-(U$1-PadP$62)") (class "Default")
      (node (ref "U$1") (pin "P$62") (pinfunction "P$62_P$62") (pintype "bidirectional"))
    )
    (net (code "105") (name "unconnected-(U$1-PadP$63)") (class "Default")
      (node (ref "U$1") (pin "P$63") (pinfunction "P$63_P$63") (pintype "bidirectional"))
    )
    (net (code "106") (name "unconnected-(U$1-PadP$64)") (class "Default")
      (node (ref "U$1") (pin "P$64") (pinfunction "P$64_P$64") (pintype "bidirectional"))
    )
    (net (code "107") (name "unconnected-(U$1-PadP$65)") (class "Default")
      (node (ref "U$1") (pin "P$65") (pinfunction "P$65_P$65") (pintype "bidirectional"))
    )
    (net (code "108") (name "unconnected-(U$1-PadP$66)") (class "Default")
      (node (ref "U$1") (pin "P$66") (pinfunction "P$66_P$66") (pintype "bidirectional"))
    )
    (net (code "109") (name "unconnected-(U$1-PadP$67)") (class "Default")
      (node (ref "U$1") (pin "P$67") (pinfunction "P$67_P$67") (pintype "bidirectional"))
    )
    (net (code "110") (name "unconnected-(U$1-PadP$68)") (class "Default")
      (node (ref "U$1") (pin "P$68") (pinfunction "P$68_P$68") (pintype "bidirectional"))
    )
    (net (code "111") (name "unconnected-(U$1-PadP$73)") (class "Default")
      (node (ref "U$1") (pin "P$73") (pinfunction "P$73_P$73") (pintype "bidirectional"))
    )
    (net (code "112") (name "unconnected-(U$1-PadP$74)") (class "Default")
      (node (ref "U$1") (pin "P$74") (pinfunction "P$74_P$74") (pintype "bidirectional"))
    )
    (net (code "113") (name "unconnected-(U$1-PadP$75)") (class "Default")
      (node (ref "U$1") (pin "P$75") (pinfunction "P$75_P$75") (pintype "bidirectional"))
    )
    (net (code "114") (name "unconnected-(U$1-PadP$76)") (class "Default")
      (node (ref "U$1") (pin "P$76") (pinfunction "P$76_P$76") (pintype "bidirectional"))
    )
    (net (code "115") (name "unconnected-(U$1-PadP$81)") (class "Default")
      (node (ref "U$1") (pin "P$81") (pinfunction "P$81_P$81") (pintype "bidirectional"))
    )
    (net (code "116") (name "unconnected-(U$1-PadP$82)") (class "Default")
      (node (ref "U$1") (pin "P$82") (pinfunction "P$82_P$82") (pintype "bidirectional"))
    )
    (net (code "117") (name "unconnected-(U$1-PadP$83)") (class "Default")
      (node (ref "U$1") (pin "P$83") (pinfunction "P$83_P$83") (pintype "bidirectional"))
    )
    (net (code "118") (name "unconnected-(U$1-PadP$84)") (class "Default")
      (node (ref "U$1") (pin "P$84") (pinfunction "P$84_P$84") (pintype "bidirectional"))
    )
    (net (code "119") (name "unconnected-(U$1-PadP$89)") (class "Default")
      (node (ref "U$1") (pin "P$89") (pinfunction "P$89_P$89") (pintype "bidirectional"))
    )
    (net (code "120") (name "unconnected-(U$1-PadP$90)") (class "Default")
      (node (ref "U$1") (pin "P$90") (pinfunction "P$90_P$90") (pintype "bidirectional"))
    )
    (net (code "121") (name "unconnected-(U$1-PadP$91)") (class "Default")
      (node (ref "U$1") (pin "P$91") (pinfunction "P$91_P$91") (pintype "bidirectional"))
    )
    (net (code "122") (name "unconnected-(U$1-PadP$92)") (class "Default")
      (node (ref "U$1") (pin "P$92") (pinfunction "P$92_P$92") (pintype "bidirectional"))
    )
    (net (code "123") (name "unconnected-(U$1-PadP$95)") (class "Default")
      (node (ref "U$1") (pin "P$95") (pinfunction "P$95_P$95") (pintype "bidirectional"))
    )
    (net (code "124") (name "unconnected-(U$1-PadP$96)") (class "Default")
      (node (ref "U$1") (pin "P$96") (pinfunction "P$96_P$96") (pintype "bidirectional"))
    )
    (net (code "125") (name "unconnected-(U$1-RAHS_GND-PadP$94)") (class "Default")
      (node (ref "U$1") (pin "P$94") (pinfunction "RAHS_GND_P$94") (pintype "bidirectional"))
    )
    (net (code "126") (name "unconnected-(U$1-RAHS_VBAT-PadP$93)") (class "Default")
      (node (ref "U$1") (pin "P$93") (pinfunction "RAHS_VBAT_P$93") (pintype "bidirectional"))
    )
    (net (code "127") (name "unconnected-(U$1-TOPDEPLOY+-PadP$51)") (class "Default")
      (node (ref "U$1") (pin "P$51") (pinfunction "TOPDEPLOY+_P$51") (pintype "bidirectional"))
    )
    (net (code "128") (name "unconnected-(U$1-TOPDEPLOY+-PadP$55)") (class "Default")
      (node (ref "U$1") (pin "P$55") (pinfunction "TOPDEPLOY+_P$55") (pintype "bidirectional"))
    )
    (net (code "129") (name "unconnected-(U$1-TOPDEPLOY-$52-PadP$52)") (class "Default")
      (node (ref "U$1") (pin "P$52") (pinfunction "TOPDEPLOY-$52_P$52") (pintype "bidirectional"))
    )
    (net (code "130") (name "unconnected-(U$1-TOPDEPLOY-$56-PadP$56)") (class "Default")
      (node (ref "U$1") (pin "P$56") (pinfunction "TOPDEPLOY-$56_P$56") (pintype "bidirectional"))
    )
    (net (code "131") (name "unconnected-(U$1-WHEEL_GND-PadP$71)") (class "Default")
      (node (ref "U$1") (pin "P$71") (pinfunction "WHEEL_GND_P$71") (pintype "bidirectional"))
    )
    (net (code "132") (name "unconnected-(U$1-WHEEL_GND-PadP$72)") (class "Default")
      (node (ref "U$1") (pin "P$72") (pinfunction "WHEEL_GND_P$72") (pintype "bidirectional"))
    )
    (net (code "133") (name "unconnected-(U$1-WHEEL_VBAT-PadP$69)") (class "Default")
      (node (ref "U$1") (pin "P$69") (pinfunction "WHEEL_VBAT_P$69") (pintype "bidirectional"))
    )
    (net (code "134") (name "unconnected-(U$1-WHEEL_VBAT-PadP$70)") (class "Default")
      (node (ref "U$1") (pin "P$70") (pinfunction "WHEEL_VBAT_P$70") (pintype "bidirectional"))
    )
    (net (code "135") (name "unconnected-(U$7-P2.3_SPI-CS2-PadP2.4_SPI-CS2)") (class "Default")
      (node (ref "U$7") (pin "P2.4_SPI-CS2") (pinfunction "P2.3_SPI-CS2_P2.4_SPI-CS2") (pintype "bidirectional"))
    )
    (net (code "136") (name "unconnected-(U$7-PadP1.0_A0)") (class "Default")
      (node (ref "U$7") (pin "P1.0_A0") (pinfunction "P1.0_A0_P1.0_A0") (pintype "bidirectional"))
    )
    (net (code "137") (name "unconnected-(U$7-PadP1.1_A1)") (class "Default")
      (node (ref "U$7") (pin "P1.1_A1") (pinfunction "P1.1_A1_P1.1_A1") (pintype "bidirectional"))
    )
    (net (code "138") (name "unconnected-(U$7-PadP1.2_A2)") (class "Default")
      (node (ref "U$7") (pin "P1.2_A2") (pinfunction "P1.2_A2_P1.2_A2") (pintype "bidirectional"))
    )
    (net (code "139") (name "unconnected-(U$7-PadP1.3_A3)") (class "Default")
      (node (ref "U$7") (pin "P1.3_A3") (pinfunction "P1.3_A3_P1.3_A3") (pintype "bidirectional"))
    )
    (net (code "140") (name "unconnected-(U$7-PadP1.4_A4)") (class "Default")
      (node (ref "U$7") (pin "P1.4_A4") (pinfunction "P1.4_A4_P1.4_A4") (pintype "bidirectional"))
    )
    (net (code "141") (name "unconnected-(U$7-PadP1.5_A5)") (class "Default")
      (node (ref "U$7") (pin "P1.5_A5") (pinfunction "P1.5_A5_P1.5_A5") (pintype "bidirectional"))
    )
    (net (code "142") (name "unconnected-(U$7-PadP2.5_GPIO)") (class "Default")
      (node (ref "U$7") (pin "P2.5_GPIO") (pinfunction "P2.5_GPIO_P2.5_GPIO") (pintype "bidirectional"))
    )
    (net (code "143") (name "unconnected-(U$7-PadP2.7_SPI-CS3)") (class "Default")
      (node (ref "U$7") (pin "P2.7_SPI-CS3") (pinfunction "P2.7_SPI-CS3_P2.7_SPI-CS3") (pintype "bidirectional"))
    )
    (net (code "144") (name "unconnected-(U$7-PadP3.0_A12)") (class "Default")
      (node (ref "U$7") (pin "P3.0_A12") (pinfunction "P3.0_A12_P3.0_A12") (pintype "bidirectional"))
    )
    (net (code "145") (name "unconnected-(U$7-PadP3.1_A13)") (class "Default")
      (node (ref "U$7") (pin "P3.1_A13") (pinfunction "P3.1_A13_P3.1_A13") (pintype "bidirectional"))
    )
    (net (code "146") (name "unconnected-(U$7-PadP3.2_A14)") (class "Default")
      (node (ref "U$7") (pin "P3.2_A14") (pinfunction "P3.2_A14_P3.2_A14") (pintype "bidirectional"))
    )
    (net (code "147") (name "unconnected-(U$7-PadP3.3_A15)") (class "Default")
      (node (ref "U$7") (pin "P3.3_A15") (pinfunction "P3.3_A15_P3.3_A15") (pintype "bidirectional"))
    )
    (net (code "148") (name "unconnected-(U$7-PadP4.0_GPIO)") (class "Default")
      (node (ref "U$7") (pin "P4.0_GPIO") (pinfunction "P4.0_GPIO_P4.0_GPIO") (pintype "bidirectional"))
    )
    (net (code "149") (name "unconnected-(U$7-PadP4.1_GPIO)") (class "Default")
      (node (ref "U$7") (pin "P4.1_GPIO") (pinfunction "P4.1_GPIO_P4.1_GPIO") (pintype "bidirectional"))
    )
    (net (code "150") (name "unconnected-(U$7-PadP4.2_GPIO)") (class "Default")
      (node (ref "U$7") (pin "P4.2_GPIO") (pinfunction "P4.2_GPIO_P4.2_GPIO") (pintype "bidirectional"))
    )
    (net (code "151") (name "unconnected-(U$7-PadP4.3_GPIO)") (class "Default")
      (node (ref "U$7") (pin "P4.3_GPIO") (pinfunction "P4.3_GPIO_P4.3_GPIO") (pintype "bidirectional"))
    )
    (net (code "152") (name "unconnected-(U$7-PadP5.0_I2C-SDA-1)") (class "Default")
      (node (ref "U$7") (pin "P5.0_I2C-SDA-1") (pinfunction "P5.0_I2C-SDA-1_P5.0_I2C-SDA-1") (pintype "bidirectional"))
    )
    (net (code "153") (name "unconnected-(U$7-PadP5.1_I2C-SCL-1)") (class "Default")
      (node (ref "U$7") (pin "P5.1_I2C-SCL-1") (pinfunction "P5.1_I2C-SCL-1_P5.1_I2C-SCL-1") (pintype "bidirectional"))
    )
    (net (code "154") (name "unconnected-(U$7-PadP5.4_SPI-MOSI)") (class "Default")
      (node (ref "U$7") (pin "P5.4_SPI-MOSI") (pinfunction "P5.4_SPI-MOSI_P5.4_SPI-MOSI") (pintype "bidirectional"))
    )
    (net (code "155") (name "unconnected-(U$7-PadP5.5_SPI-MISO)") (class "Default")
      (node (ref "U$7") (pin "P5.5_SPI-MISO") (pinfunction "P5.5_SPI-MISO_P5.5_SPI-MISO") (pintype "bidirectional"))
    )
    (net (code "156") (name "unconnected-(U$7-PadP5.6_SPI-CLK)") (class "Default")
      (node (ref "U$7") (pin "P5.6_SPI-CLK") (pinfunction "P5.6_SPI-CLK_P5.6_SPI-CLK") (pintype "bidirectional"))
    )
    (net (code "157") (name "unconnected-(U$7-PadP7.0_I2C-SDA-2)") (class "Default")
      (node (ref "U$7") (pin "P7.0_I2C-SDA-2") (pinfunction "P7.0_I2C-SDA-2_P7.0_I2C-SDA-2") (pintype "bidirectional"))
    )
    (net (code "158") (name "unconnected-(U$7-PadP7.1_I2C-SCL-2)") (class "Default")
      (node (ref "U$7") (pin "P7.1_I2C-SCL-2") (pinfunction "P7.1_I2C-SCL-2_P7.1_I2C-SCL-2") (pintype "bidirectional"))
    )
    (net (code "159") (name "unconnected-(U$7-PadP7.3_GPIO)") (class "Default")
      (node (ref "U$7") (pin "P7.3_GPIO") (pinfunction "P7.3_GPIO_P7.3_GPIO") (pintype "bidirectional"))
    )
    (net (code "160") (name "unconnected-(U$7-PadP7.4_GPIO)") (class "Default")
      (node (ref "U$7") (pin "P7.4_GPIO") (pinfunction "P7.4_GPIO_P7.4_GPIO") (pintype "bidirectional"))
    )
    (net (code "161") (name "unconnected-(U$9-NC-PadP$2)") (class "Default")
      (node (ref "U$9") (pin "P$2") (pinfunction "NC_P$2") (pintype "bidirectional"))
    )
  )
)
